# sch_AGV_Communication.net
KiCad netlist of a schematic drawn in Altium Designer
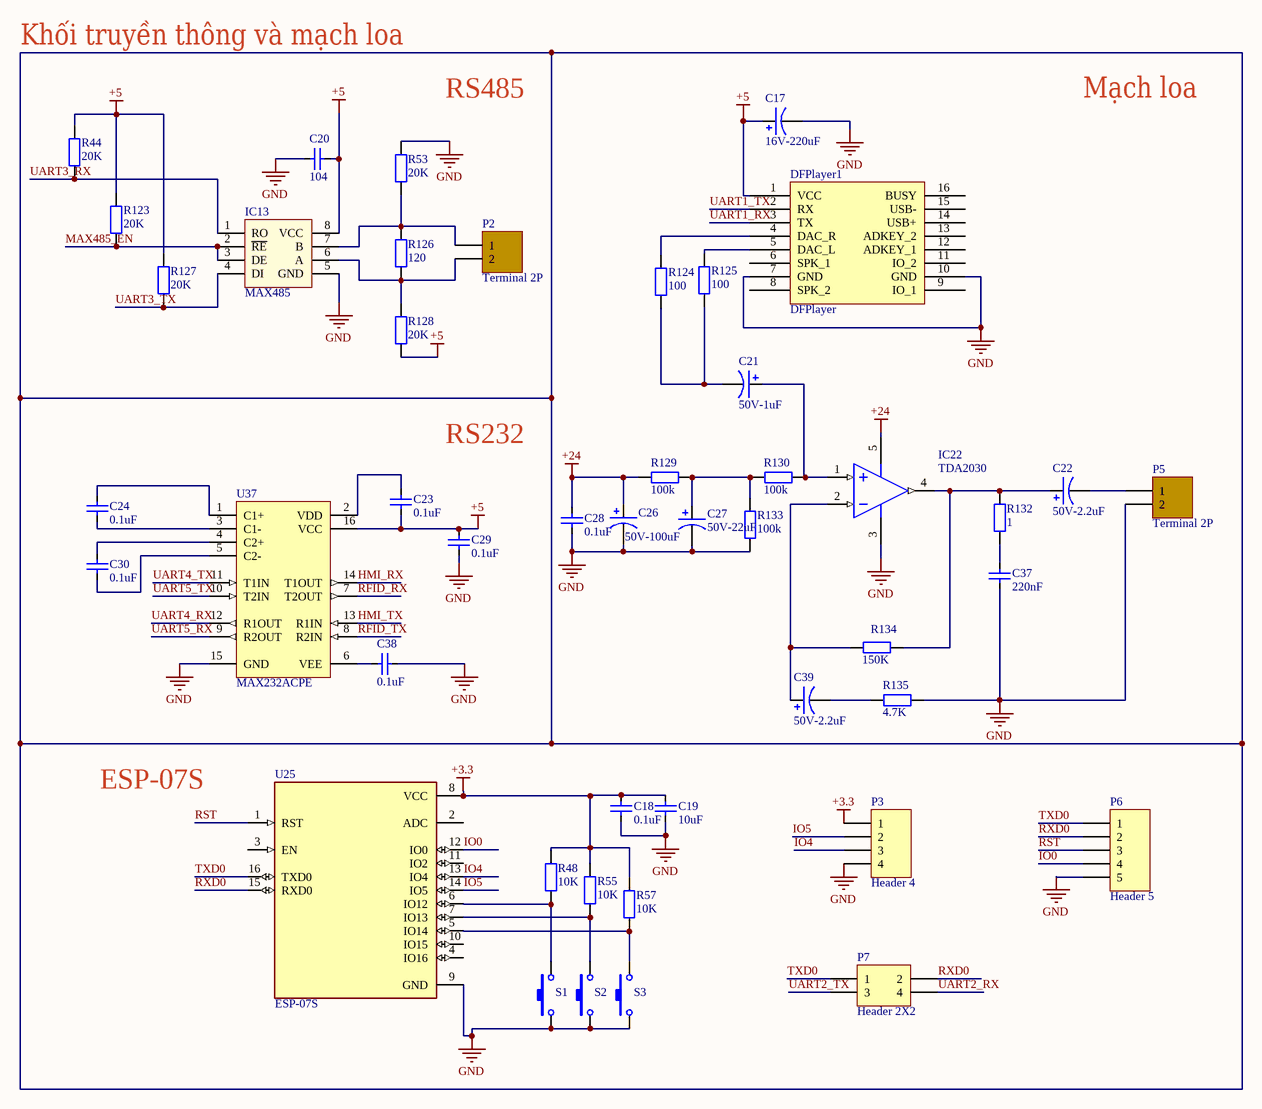
[diagram p0: sch_AGV_Communication.SchDoc]

(export (version "E")
  (design (tool "Eeschema 10.0.6"))
  (components
    (comp (ref "C17")
      (value "16V-220uF")
      (footprint "CAP_D6.3")
      (description "Polarized Capacitor (Axial)")
      (fields (field (name "PUBLISHER") "Altium Limited"))
      (libsource (lib "schelib_AGVcontrol") (part "CapPol"))
    )
    (comp (ref "C18")
      (value "0.1uF")
      (footprint "CAP_0805")
      (description "Capacitor")
      (fields (field (name "PUBLISHER") "Altium Limited"))
      (libsource (lib "schelib_AGVcontrol") (part "CapSMD"))
    )
    (comp (ref "C19")
      (value "10uF")
      (footprint "CAP_0805")
      (description "Capacitor")
      (fields (field (name "PUBLISHER") "Altium Limited"))
      (libsource (lib "schelib_AGVcontrol") (part "CapSMD"))
    )
    (comp (ref "C20")
      (value "104")
      (footprint "CAP_0805")
      (description "Capacitor")
      (fields (field (name "PUBLISHER") "Altium Limited"))
      (libsource (lib "schelib_AGVcontrol") (part "CapSMD"))
    )
    (comp (ref "C21")
      (value "50V-1uF")
      (footprint "CAP_D5")
      (description "Polarized Capacitor (Axial)")
      (fields (field (name "PUBLISHER") "Altium Limited"))
      (libsource (lib "schelib_AGVcontrol") (part "CapPol"))
    )
    (comp (ref "C22")
      (value "50V-2.2uF")
      (footprint "CAP_D5")
      (description "Polarized Capacitor (Axial)")
      (fields (field (name "PUBLISHER") "Altium Limited"))
      (libsource (lib "schelib_AGVcontrol") (part "CapPol"))
    )
    (comp (ref "C23")
      (value "0.1uF")
      (footprint "CAP_0805")
      (description "Capacitor")
      (fields (field (name "PUBLISHER") "Altium Limited"))
      (libsource (lib "schelib_AGVcontrol") (part "CapSMD"))
    )
    (comp (ref "C24")
      (value "0.1uF")
      (footprint "CAP_0805")
      (description "Capacitor")
      (fields (field (name "PUBLISHER") "Altium Limited"))
      (libsource (lib "schelib_AGVcontrol") (part "CapSMD"))
    )
    (comp (ref "C26")
      (value "50V-100uF")
      (footprint "CAP_D8")
      (description "Polarized Capacitor (Axial)")
      (fields (field (name "PUBLISHER") "Altium Limited"))
      (libsource (lib "schelib_AGVcontrol") (part "CapPol"))
    )
    (comp (ref "C27")
      (value "50V-22uF")
      (footprint "CAP_D5")
      (description "Polarized Capacitor (Axial)")
      (fields (field (name "PUBLISHER") "Altium Limited"))
      (libsource (lib "schelib_AGVcontrol") (part "CapPol"))
    )
    (comp (ref "C28")
      (value "0.1uF")
      (footprint "CAP_0805")
      (description "Capacitor")
      (fields (field (name "PUBLISHER") "Altium Limited"))
      (libsource (lib "schelib_AGVcontrol") (part "CapSMD"))
    )
    (comp (ref "C29")
      (value "0.1uF")
      (footprint "CAP_0805")
      (description "Capacitor")
      (fields (field (name "PUBLISHER") "Altium Limited"))
      (libsource (lib "schelib_AGVcontrol") (part "CapSMD"))
    )
    (comp (ref "C30")
      (value "0.1uF")
      (footprint "CAP_0805")
      (description "Capacitor")
      (fields (field (name "PUBLISHER") "Altium Limited"))
      (libsource (lib "schelib_AGVcontrol") (part "CapSMD"))
    )
    (comp (ref "C37")
      (value "220nF")
      (footprint "CAP_0805")
      (description "Capacitor")
      (fields (field (name "PUBLISHER") "Altium Limited"))
      (libsource (lib "schelib_AGVcontrol") (part "CapSMD"))
    )
    (comp (ref "C38")
      (value "0.1uF")
      (footprint "CAP_0805")
      (description "Capacitor")
      (fields (field (name "PUBLISHER") "Altium Limited"))
      (libsource (lib "schelib_AGVcontrol") (part "CapSMD"))
    )
    (comp (ref "C39")
      (value "50V-2.2uF")
      (footprint "CAP_D5")
      (description "Polarized Capacitor (Axial)")
      (fields (field (name "PUBLISHER") "Altium Limited"))
      (libsource (lib "schelib_AGVcontrol") (part "CapPol"))
    )
    (comp (ref "DFPlayer1")
      (value "DFPlayer")
      (footprint "DFPlayer")
      (libsource (lib "schelib_AGVcontrol") (part "DFPlayer"))
    )
    (comp (ref "IC13")
      (value "MAX485")
      (footprint "SOP8-PP")
      (description "RS232 - RS485 (Same sn75176)")
      (libsource (lib "schelib_AGVcontrol") (part "MAX485"))
    )
    (comp (ref "IC22")
      (value "TDA2030")
      (footprint "DIP5SL1")
      (description "14W Hi-Fi AUDIO AMPLIFIER")
      (libsource (lib "schelib_AGVcontrol") (part "TDA2030"))
    )
    (comp (ref "P2")
      (value "Terminal 2P")
      (footprint "BIG_Header 2")
      (description "Terminal 5.08")
      (fields (field (name "PUBLISHER") "Altium Limited"))
      (libsource (lib "schelib_AGVcontrol") (part "Terminal 2P"))
    )
    (comp (ref "P3")
      (value "Header 4")
      (footprint "HDR4")
      (description "Header, 4-Pin")
      (fields (field (name "PUBLISHER") "Altium Limited"))
      (libsource (lib "schelib_AGVcontrol") (part "Header 4"))
    )
    (comp (ref "P5")
      (value "Terminal 2P")
      (footprint "BIG_Header 2")
      (description "Terminal 5.08")
      (fields (field (name "PUBLISHER") "Altium Limited"))
      (libsource (lib "schelib_AGVcontrol") (part "Terminal 2P"))
    )
    (comp (ref "P6")
      (value "Header 5")
      (footprint "HDR5")
      (description "Header, 5-Pin")
      (fields (field (name "PUBLISHER") "Altium Limited"))
      (libsource (lib "schelib_AGVcontrol") (part "Header 5"))
    )
    (comp (ref "P7")
      (value "Header 2X2")
      (footprint "JP2X2")
      (description "Header, 2-Pin, Dual row")
      (fields (field (name "PUBLISHER") "Altium Limited"))
      (libsource (lib "schelib_AGVcontrol") (part "Header 2X2"))
    )
    (comp (ref "R44")
      (value "20K")
      (footprint "RES_SMD_0805")
      (description "Resistor")
      (fields
        (field (name "MANUFACTURER") "Generic Components")
        (field (name "PUBLISHER") "Altium Hobart Technology Centre")
      )
      (libsource (lib "schelib_AGVcontrol") (part "Res"))
    )
    (comp (ref "R48")
      (value "10K")
      (footprint "RES_SMD_0805")
      (description "Resistor")
      (fields
        (field (name "MANUFACTURER") "Generic Components")
        (field (name "PUBLISHER") "Altium Hobart Technology Centre")
      )
      (libsource (lib "schelib_AGVcontrol") (part "Res"))
    )
    (comp (ref "R53")
      (value "20K")
      (footprint "RES_SMD_0805")
      (description "Resistor")
      (fields
        (field (name "MANUFACTURER") "Generic Components")
        (field (name "PUBLISHER") "Altium Hobart Technology Centre")
      )
      (libsource (lib "schelib_AGVcontrol") (part "Res"))
    )
    (comp (ref "R55")
      (value "10K")
      (footprint "RES_SMD_0805")
      (description "Resistor")
      (fields
        (field (name "MANUFACTURER") "Generic Components")
        (field (name "PUBLISHER") "Altium Hobart Technology Centre")
      )
      (libsource (lib "schelib_AGVcontrol") (part "Res"))
    )
    (comp (ref "R57")
      (value "10K")
      (footprint "RES_SMD_0805")
      (description "Resistor")
      (fields
        (field (name "MANUFACTURER") "Generic Components")
        (field (name "PUBLISHER") "Altium Hobart Technology Centre")
      )
      (libsource (lib "schelib_AGVcontrol") (part "Res"))
    )
    (comp (ref "R123")
      (value "20K")
      (footprint "RES_SMD_0805")
      (description "Resistor")
      (fields
        (field (name "MANUFACTURER") "Generic Components")
        (field (name "PUBLISHER") "Altium Hobart Technology Centre")
      )
      (libsource (lib "schelib_AGVcontrol") (part "Res"))
    )
    (comp (ref "R124")
      (value "100")
      (footprint "RES_1/4 W")
      (description "Resistor")
      (fields
        (field (name "MANUFACTURER") "Generic Components")
        (field (name "PUBLISHER") "Altium Hobart Technology Centre")
      )
      (libsource (lib "schelib_AGVcontrol") (part "Res"))
    )
    (comp (ref "R125")
      (value "100")
      (footprint "RES_1/4 W")
      (description "Resistor")
      (fields
        (field (name "MANUFACTURER") "Generic Components")
        (field (name "PUBLISHER") "Altium Hobart Technology Centre")
      )
      (libsource (lib "schelib_AGVcontrol") (part "Res"))
    )
    (comp (ref "R126")
      (value "120")
      (footprint "RES_SMD_0805")
      (description "Resistor")
      (fields
        (field (name "MANUFACTURER") "Generic Components")
        (field (name "PUBLISHER") "Altium Hobart Technology Centre")
      )
      (libsource (lib "schelib_AGVcontrol") (part "Res"))
    )
    (comp (ref "R127")
      (value "20K")
      (footprint "RES_SMD_0805")
      (description "Resistor")
      (fields
        (field (name "MANUFACTURER") "Generic Components")
        (field (name "PUBLISHER") "Altium Hobart Technology Centre")
      )
      (libsource (lib "schelib_AGVcontrol") (part "Res"))
    )
    (comp (ref "R128")
      (value "20K")
      (footprint "RES_SMD_0805")
      (description "Resistor")
      (fields
        (field (name "MANUFACTURER") "Generic Components")
        (field (name "PUBLISHER") "Altium Hobart Technology Centre")
      )
      (libsource (lib "schelib_AGVcontrol") (part "Res"))
    )
    (comp (ref "R129")
      (value "100k")
      (footprint "RES_1/4 W")
      (description "Resistor")
      (fields
        (field (name "MANUFACTURER") "Generic Components")
        (field (name "PUBLISHER") "Altium Hobart Technology Centre")
      )
      (libsource (lib "schelib_AGVcontrol") (part "Res"))
    )
    (comp (ref "R130")
      (value "100k")
      (footprint "RES_1/4 W")
      (description "Resistor")
      (fields
        (field (name "MANUFACTURER") "Generic Components")
        (field (name "PUBLISHER") "Altium Hobart Technology Centre")
      )
      (libsource (lib "schelib_AGVcontrol") (part "Res"))
    )
    (comp (ref "R132")
      (value "1")
      (footprint "RES_1/4 W")
      (description "Resistor")
      (fields
        (field (name "MANUFACTURER") "Generic Components")
        (field (name "PUBLISHER") "Altium Hobart Technology Centre")
      )
      (libsource (lib "schelib_AGVcontrol") (part "Res"))
    )
    (comp (ref "R133")
      (value "100k")
      (footprint "RES_1/4 W")
      (description "Resistor")
      (fields
        (field (name "MANUFACTURER") "Generic Components")
        (field (name "PUBLISHER") "Altium Hobart Technology Centre")
      )
      (libsource (lib "schelib_AGVcontrol") (part "Res"))
    )
    (comp (ref "R134")
      (value "150K")
      (footprint "RES_1/4 W")
      (description "Resistor")
      (fields
        (field (name "MANUFACTURER") "Generic Components")
        (field (name "PUBLISHER") "Altium Hobart Technology Centre")
      )
      (libsource (lib "schelib_AGVcontrol") (part "Res"))
    )
    (comp (ref "R135")
      (value "4.7K")
      (footprint "RES_1/4 W")
      (description "Resistor")
      (fields
        (field (name "MANUFACTURER") "Generic Components")
        (field (name "PUBLISHER") "Altium Hobart Technology Centre")
      )
      (libsource (lib "schelib_AGVcontrol") (part "Res"))
    )
    (comp (ref "S1")
      (value "SW-SMD")
      (footprint "BUTTON 4 PIN")
      (description "Switch")
      (fields (field (name "PUBLISHER") "Altium Limited"))
      (libsource (lib "schelib_AGVcontrol") (part "SW-SMD"))
    )
    (comp (ref "S2")
      (value "SW-SMD")
      (footprint "BUTTON 4 PIN")
      (description "Switch")
      (fields (field (name "PUBLISHER") "Altium Limited"))
      (libsource (lib "schelib_AGVcontrol") (part "SW-SMD"))
    )
    (comp (ref "S3")
      (value "SW-SMD")
      (footprint "BUTTON 4 PIN")
      (description "Switch")
      (fields (field (name "PUBLISHER") "Altium Limited"))
      (libsource (lib "schelib_AGVcontrol") (part "SW-SMD"))
    )
    (comp (ref "U25")
      (value "ESP-07S")
      (footprint "XCVR_ESP-07S")
      (description "WiFi 802.11b/g/n Transceiver Module 2.4GHz ~ 2.5GHz PCB Trace Surface Mount")
      (fields (field (name "MF") "RF Solutions"))
      (libsource (lib "schelib_AGVcontrol") (part "ESP-07S"))
    )
    (comp (ref "U37")
      (value "MAX232ACPE")
      (footprint "DIP.100/16/W.300/L.900")
      (description "+5V Powered, Multi-Channel RS-232 Driver/Receiver")
      (fields (field (name "PUBLISHER") "Altium Limited"))
      (libsource (lib "schelib_AGVcontrol") (part "MAX232ACPE"))
    )
  )
  (nets
    (net (code "1") (name "+3.3") (class "Default")
      (node (ref "C18") (pin "2") (pinfunction "2_2") (pintype "passive"))
      (node (ref "C19") (pin "2") (pinfunction "2_2") (pintype "passive"))
      (node (ref "P3") (pin "1") (pinfunction "1_1") (pintype "passive"))
      (node (ref "R48") (pin "1") (pinfunction "1_1") (pintype "passive"))
      (node (ref "R55") (pin "1") (pinfunction "1_1") (pintype "passive"))
      (node (ref "R57") (pin "1") (pinfunction "1_1") (pintype "passive"))
      (node (ref "U25") (pin "8") (pinfunction "VCC_8") (pintype "power_in"))
    )
    (net (code "2") (name "+5") (class "Default")
      (node (ref "C17") (pin "1") (pinfunction "1_1") (pintype "passive"))
      (node (ref "C20") (pin "2") (pinfunction "2_2") (pintype "passive"))
      (node (ref "C23") (pin "1") (pinfunction "1_1") (pintype "passive"))
      (node (ref "C29") (pin "2") (pinfunction "2_2") (pintype "passive"))
      (node (ref "DFPlayer1") (pin "1") (pinfunction "VCC_1") (pintype "passive"))
      (node (ref "IC13") (pin "8") (pinfunction "VCC_8") (pintype "passive"))
      (node (ref "R123") (pin "2") (pinfunction "2_2") (pintype "passive"))
      (node (ref "R127") (pin "1") (pinfunction "1_1") (pintype "passive"))
      (node (ref "R128") (pin "2") (pinfunction "2_2") (pintype "passive"))
      (node (ref "R44") (pin "1") (pinfunction "1_1") (pintype "passive"))
      (node (ref "U37") (pin "16") (pinfunction "VCC_16") (pintype "power_in"))
    )
    (net (code "3") (name "+24") (class "Default")
      (node (ref "C26") (pin "1") (pinfunction "1_1") (pintype "passive"))
      (node (ref "C28") (pin "2") (pinfunction "2_2") (pintype "passive"))
      (node (ref "IC22") (pin "5") (pinfunction "V+_5") (pintype "power_in"))
      (node (ref "R129") (pin "2") (pinfunction "2_2") (pintype "passive"))
    )
    (net (code "4") (name "/HMI_RX") (class "Default")
      (node (ref "U37") (pin "14") (pinfunction "T1OUT_14") (pintype "output"))
    )
    (net (code "5") (name "/HMI_TX") (class "Default")
      (node (ref "U37") (pin "13") (pinfunction "R1IN_13") (pintype "input"))
    )
    (net (code "6") (name "/IO0") (class "Default")
      (node (ref "P6") (pin "4") (pinfunction "4_4") (pintype "passive"))
      (node (ref "U25") (pin "12") (pinfunction "IO0_12") (pintype "bidirectional"))
    )
    (net (code "7") (name "/IO4") (class "Default")
      (node (ref "P3") (pin "3") (pinfunction "3_3") (pintype "passive"))
      (node (ref "U25") (pin "13") (pinfunction "IO4_13") (pintype "bidirectional"))
    )
    (net (code "8") (name "/IO5") (class "Default")
      (node (ref "P3") (pin "2") (pinfunction "2_2") (pintype "passive"))
      (node (ref "U25") (pin "14") (pinfunction "IO5_14") (pintype "bidirectional"))
    )
    (net (code "9") (name "/MAX485_EN") (class "Default")
      (node (ref "IC13") (pin "2") (pinfunction "~{RE}_2") (pintype "passive"))
      (node (ref "IC13") (pin "3") (pinfunction "DE_3") (pintype "passive"))
      (node (ref "R123") (pin "1") (pinfunction "1_1") (pintype "passive"))
    )
    (net (code "10") (name "/RFID_RX") (class "Default")
      (node (ref "U37") (pin "7") (pinfunction "T2OUT_7") (pintype "output"))
    )
    (net (code "11") (name "/RFID_TX") (class "Default")
      (node (ref "U37") (pin "8") (pinfunction "R2IN_8") (pintype "input"))
    )
    (net (code "12") (name "/RST") (class "Default")
      (node (ref "P6") (pin "3") (pinfunction "3_3") (pintype "passive"))
      (node (ref "U25") (pin "1") (pinfunction "RST_1") (pintype "input"))
    )
    (net (code "13") (name "/RXD0") (class "Default")
      (node (ref "P6") (pin "2") (pinfunction "2_2") (pintype "passive"))
      (node (ref "P7") (pin "2") (pinfunction "2_2") (pintype "passive"))
      (node (ref "U25") (pin "15") (pinfunction "RXD0_15") (pintype "bidirectional"))
    )
    (net (code "14") (name "/TXD0") (class "Default")
      (node (ref "P6") (pin "1") (pinfunction "1_1") (pintype "passive"))
      (node (ref "P7") (pin "1") (pinfunction "1_1") (pintype "passive"))
      (node (ref "U25") (pin "16") (pinfunction "TXD0_16") (pintype "bidirectional"))
    )
    (net (code "15") (name "/UART1_RX") (class "Default")
      (node (ref "DFPlayer1") (pin "3") (pinfunction "TX_3") (pintype "passive"))
    )
    (net (code "16") (name "/UART1_TX") (class "Default")
      (node (ref "DFPlayer1") (pin "2") (pinfunction "RX_2") (pintype "passive"))
    )
    (net (code "17") (name "/UART2_RX") (class "Default")
      (node (ref "P7") (pin "4") (pinfunction "4_4") (pintype "passive"))
    )
    (net (code "18") (name "/UART2_TX") (class "Default")
      (node (ref "P7") (pin "3") (pinfunction "3_3") (pintype "passive"))
    )
    (net (code "19") (name "/UART3_RX") (class "Default")
      (node (ref "IC13") (pin "1") (pinfunction "RO_1") (pintype "passive"))
      (node (ref "R44") (pin "2") (pinfunction "2_2") (pintype "passive"))
    )
    (net (code "20") (name "/UART3_TX") (class "Default")
      (node (ref "IC13") (pin "4") (pinfunction "DI_4") (pintype "passive"))
      (node (ref "R127") (pin "2") (pinfunction "2_2") (pintype "passive"))
    )
    (net (code "21") (name "/UART4_RX") (class "Default")
      (node (ref "U37") (pin "12") (pinfunction "R1OUT_12") (pintype "output"))
    )
    (net (code "22") (name "/UART4_TX") (class "Default")
      (node (ref "U37") (pin "11") (pinfunction "T1IN_11") (pintype "input"))
    )
    (net (code "23") (name "/UART5_RX") (class "Default")
      (node (ref "U37") (pin "9") (pinfunction "R2OUT_9") (pintype "output"))
    )
    (net (code "24") (name "/UART5_TX") (class "Default")
      (node (ref "U37") (pin "10") (pinfunction "T2IN_10") (pintype "input"))
    )
    (net (code "25") (name "GND") (class "Default")
      (node (ref "C17") (pin "2") (pinfunction "2_2") (pintype "passive"))
      (node (ref "C18") (pin "1") (pinfunction "1_1") (pintype "passive"))
      (node (ref "C19") (pin "1") (pinfunction "1_1") (pintype "passive"))
      (node (ref "C20") (pin "1") (pinfunction "1_1") (pintype "passive"))
      (node (ref "C26") (pin "2") (pinfunction "2_2") (pintype "passive"))
      (node (ref "C27") (pin "2") (pinfunction "2_2") (pintype "passive"))
      (node (ref "C28") (pin "1") (pinfunction "1_1") (pintype "passive"))
      (node (ref "C29") (pin "1") (pinfunction "1_1") (pintype "passive"))
      (node (ref "C37") (pin "1") (pinfunction "1_1") (pintype "passive"))
      (node (ref "C38") (pin "1") (pinfunction "1_1") (pintype "passive"))
      (node (ref "DFPlayer1") (pin "10") (pinfunction "GND_10") (pintype "passive"))
      (node (ref "DFPlayer1") (pin "7") (pinfunction "GND_7") (pintype "passive"))
      (node (ref "IC13") (pin "5") (pinfunction "GND_5") (pintype "passive"))
      (node (ref "IC22") (pin "3") (pinfunction "V-_3") (pintype "power_in"))
      (node (ref "P3") (pin "4") (pinfunction "4_4") (pintype "passive"))
      (node (ref "P5") (pin "2") (pinfunction "2_2") (pintype "passive"))
      (node (ref "P6") (pin "5") (pinfunction "5_5") (pintype "passive"))
      (node (ref "R133") (pin "2") (pinfunction "2_2") (pintype "passive"))
      (node (ref "R135") (pin "1") (pinfunction "1_1") (pintype "passive"))
      (node (ref "R53") (pin "1") (pinfunction "1_1") (pintype "passive"))
      (node (ref "S1") (pin "1") (pinfunction "1_1") (pintype "passive"))
      (node (ref "S2") (pin "1") (pinfunction "1_1") (pintype "passive"))
      (node (ref "S3") (pin "1") (pinfunction "1_1") (pintype "passive"))
      (node (ref "U25") (pin "9") (pinfunction "GND_9") (pintype "power_in"))
      (node (ref "U37") (pin "15") (pinfunction "GND_15") (pintype "power_in"))
    )
    (net (code "26") (name "Net-(C21-Pad2)") (class "Default")
      (node (ref "C21") (pin "2") (pinfunction "2_2") (pintype "passive"))
      (node (ref "R124") (pin "2") (pinfunction "2_2") (pintype "passive"))
      (node (ref "R125") (pin "2") (pinfunction "2_2") (pintype "passive"))
    )
    (net (code "27") (name "Net-(C22-Pad2)") (class "Default")
      (node (ref "C22") (pin "2") (pinfunction "2_2") (pintype "passive"))
      (node (ref "P5") (pin "1") (pinfunction "1_1") (pintype "passive"))
    )
    (net (code "28") (name "Net-(C27-Pad1)") (class "Default")
      (node (ref "C27") (pin "1") (pinfunction "1_1") (pintype "passive"))
      (node (ref "R129") (pin "1") (pinfunction "1_1") (pintype "passive"))
      (node (ref "R130") (pin "2") (pinfunction "2_2") (pintype "passive"))
      (node (ref "R133") (pin "1") (pinfunction "1_1") (pintype "passive"))
    )
    (net (code "29") (name "Net-(C37-Pad2)") (class "Default")
      (node (ref "C37") (pin "2") (pinfunction "2_2") (pintype "passive"))
      (node (ref "R132") (pin "2") (pinfunction "2_2") (pintype "passive"))
    )
    (net (code "30") (name "Net-(C39-Pad2)") (class "Default")
      (node (ref "C39") (pin "2") (pinfunction "2_2") (pintype "passive"))
      (node (ref "R135") (pin "2") (pinfunction "2_2") (pintype "passive"))
    )
    (net (code "31") (name "Net-(DFPlayer1-DAC_L)") (class "Default")
      (node (ref "DFPlayer1") (pin "5") (pinfunction "DAC_L_5") (pintype "passive"))
      (node (ref "R125") (pin "1") (pinfunction "1_1") (pintype "passive"))
    )
    (net (code "32") (name "Net-(DFPlayer1-DAC_R)") (class "Default")
      (node (ref "DFPlayer1") (pin "4") (pinfunction "DAC_R_4") (pintype "passive"))
      (node (ref "R124") (pin "1") (pinfunction "1_1") (pintype "passive"))
    )
    (net (code "33") (name "Net-(IC13-A)") (class "Default")
      (node (ref "IC13") (pin "6") (pinfunction "A_6") (pintype "passive"))
      (node (ref "P2") (pin "2") (pinfunction "2_2") (pintype "passive"))
      (node (ref "R126") (pin "2") (pinfunction "2_2") (pintype "passive"))
      (node (ref "R128") (pin "1") (pinfunction "1_1") (pintype "passive"))
    )
    (net (code "34") (name "Net-(IC13-B)") (class "Default")
      (node (ref "IC13") (pin "7") (pinfunction "B_7") (pintype "passive"))
      (node (ref "P2") (pin "1") (pinfunction "1_1") (pintype "passive"))
      (node (ref "R126") (pin "1") (pinfunction "1_1") (pintype "passive"))
      (node (ref "R53") (pin "2") (pinfunction "2_2") (pintype "passive"))
    )
    (net (code "35") (name "Net-(IC22-IN+)") (class "Default")
      (node (ref "C21") (pin "1") (pinfunction "1_1") (pintype "passive"))
      (node (ref "IC22") (pin "1") (pinfunction "IN+_1") (pintype "input"))
      (node (ref "R130") (pin "1") (pinfunction "1_1") (pintype "passive"))
    )
    (net (code "36") (name "Net-(IC22-IN-)") (class "Default")
      (node (ref "C39") (pin "1") (pinfunction "1_1") (pintype "passive"))
      (node (ref "IC22") (pin "2") (pinfunction "IN-_2") (pintype "input"))
      (node (ref "R134") (pin "2") (pinfunction "2_2") (pintype "passive"))
    )
    (net (code "37") (name "Net-(IC22-OUT)") (class "Default")
      (node (ref "C22") (pin "1") (pinfunction "1_1") (pintype "passive"))
      (node (ref "IC22") (pin "4") (pinfunction "OUT_4") (pintype "output"))
      (node (ref "R132") (pin "1") (pinfunction "1_1") (pintype "passive"))
      (node (ref "R134") (pin "1") (pinfunction "1_1") (pintype "passive"))
    )
    (net (code "38") (name "Net-(U25-IO12)") (class "Default")
      (node (ref "R48") (pin "2") (pinfunction "2_2") (pintype "passive"))
      (node (ref "S1") (pin "2") (pinfunction "2_2") (pintype "passive"))
      (node (ref "U25") (pin "6") (pinfunction "IO12_6") (pintype "bidirectional"))
    )
    (net (code "39") (name "Net-(U25-IO13)") (class "Default")
      (node (ref "R55") (pin "2") (pinfunction "2_2") (pintype "passive"))
      (node (ref "S2") (pin "2") (pinfunction "2_2") (pintype "passive"))
      (node (ref "U25") (pin "7") (pinfunction "IO13_7") (pintype "bidirectional"))
    )
    (net (code "40") (name "Net-(U25-IO14)") (class "Default")
      (node (ref "R57") (pin "2") (pinfunction "2_2") (pintype "passive"))
      (node (ref "S3") (pin "2") (pinfunction "2_2") (pintype "passive"))
      (node (ref "U25") (pin "5") (pinfunction "IO14_5") (pintype "bidirectional"))
    )
    (net (code "41") (name "Net-(U37-C1+)") (class "Default")
      (node (ref "C24") (pin "2") (pinfunction "2_2") (pintype "passive"))
      (node (ref "U37") (pin "1") (pinfunction "C1+_1") (pintype "passive"))
    )
    (net (code "42") (name "Net-(U37-C1-)") (class "Default")
      (node (ref "C24") (pin "1") (pinfunction "1_1") (pintype "passive"))
      (node (ref "U37") (pin "3") (pinfunction "C1-_3") (pintype "passive"))
    )
    (net (code "43") (name "Net-(U37-C2+)") (class "Default")
      (node (ref "C30") (pin "2") (pinfunction "2_2") (pintype "passive"))
      (node (ref "U37") (pin "4") (pinfunction "C2+_4") (pintype "passive"))
    )
    (net (code "44") (name "Net-(U37-C2-)") (class "Default")
      (node (ref "C30") (pin "1") (pinfunction "1_1") (pintype "passive"))
      (node (ref "U37") (pin "5") (pinfunction "C2-_5") (pintype "passive"))
    )
    (net (code "45") (name "Net-(U37-VDD)") (class "Default")
      (node (ref "C23") (pin "2") (pinfunction "2_2") (pintype "passive"))
      (node (ref "U37") (pin "2") (pinfunction "VDD_2") (pintype "power_in"))
    )
    (net (code "46") (name "Net-(U37-VEE)") (class "Default")
      (node (ref "C38") (pin "2") (pinfunction "2_2") (pintype "passive"))
      (node (ref "U37") (pin "6") (pinfunction "VEE_6") (pintype "power_in"))
    )
    (net (code "47") (name "unconnected-(DFPlayer1-ADKEY_1-Pad12)") (class "Default")
      (node (ref "DFPlayer1") (pin "12") (pinfunction "ADKEY_1_12") (pintype "passive"))
    )
    (net (code "48") (name "unconnected-(DFPlayer1-ADKEY_2-Pad13)") (class "Default")
      (node (ref "DFPlayer1") (pin "13") (pinfunction "ADKEY_2_13") (pintype "passive"))
    )
    (net (code "49") (name "unconnected-(DFPlayer1-BUSY-Pad16)") (class "Default")
      (node (ref "DFPlayer1") (pin "16") (pinfunction "BUSY_16") (pintype "passive"))
    )
    (net (code "50") (name "unconnected-(DFPlayer1-IO_1-Pad9)") (class "Default")
      (node (ref "DFPlayer1") (pin "9") (pinfunction "IO_1_9") (pintype "passive"))
    )
    (net (code "51") (name "unconnected-(DFPlayer1-IO_2-Pad11)") (class "Default")
      (node (ref "DFPlayer1") (pin "11") (pinfunction "IO_2_11") (pintype "passive"))
    )
    (net (code "52") (name "unconnected-(DFPlayer1-SPK_1-Pad6)") (class "Default")
      (node (ref "DFPlayer1") (pin "6") (pinfunction "SPK_1_6") (pintype "passive"))
    )
    (net (code "53") (name "unconnected-(DFPlayer1-SPK_2-Pad8)") (class "Default")
      (node (ref "DFPlayer1") (pin "8") (pinfunction "SPK_2_8") (pintype "passive"))
    )
    (net (code "54") (name "unconnected-(DFPlayer1-USB+-Pad14)") (class "Default")
      (node (ref "DFPlayer1") (pin "14") (pinfunction "USB+_14") (pintype "passive"))
    )
    (net (code "55") (name "unconnected-(DFPlayer1-USB--Pad15)") (class "Default")
      (node (ref "DFPlayer1") (pin "15") (pinfunction "USB-_15") (pintype "passive"))
    )
    (net (code "56") (name "unconnected-(U25-ADC-Pad2)") (class "Default")
      (node (ref "U25") (pin "2") (pinfunction "ADC_2") (pintype "passive"))
    )
    (net (code "57") (name "unconnected-(U25-EN-Pad3)") (class "Default")
      (node (ref "U25") (pin "3") (pinfunction "EN_3") (pintype "input"))
    )
    (net (code "58") (name "unconnected-(U25-IO2-Pad11)") (class "Default")
      (node (ref "U25") (pin "11") (pinfunction "IO2_11") (pintype "bidirectional"))
    )
    (net (code "59") (name "unconnected-(U25-IO15-Pad10)") (class "Default")
      (node (ref "U25") (pin "10") (pinfunction "IO15_10") (pintype "bidirectional"))
    )
    (net (code "60") (name "unconnected-(U25-IO16-Pad4)") (class "Default")
      (node (ref "U25") (pin "4") (pinfunction "IO16_4") (pintype "bidirectional"))
    )
  )
)
